# schematic_vibrotactile_driver.net
KiCad netlist of a schematic drawn in EAGLE
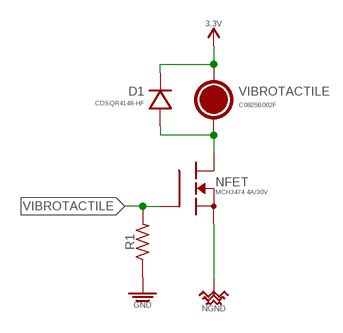
[diagram p0: schematic, sheet 1]

(export (version "E")
  (design (tool "Eeschema 10.0.6"))
  (components
    (comp (ref "D1")
      (value "CDSQR4148-HF")
      (footprint "eagle-import:DFN100X60X55-2")
      (fields (field (name "MFR") "Comchip Technology"))
      (libsource (lib "eagle-import") (part "GENERAL-PURPOSE_SMD-0402_GP_150MA-75V"))
    )
    (comp (ref "NFET")
      (value "MCH3474 4A/30V")
      (footprint "eagle-import:SOTFL65P209X90-3")
      (fields (field (name "MFR") "ON Semiconductor") (field (name "MPN") "MCH3474-TL-W"))
      (libsource (lib "eagle-import") (part "POWER_NCHAN_MCH3474_NMOS_4A-30V"))
    )
    (comp (ref "R1")
      (value "10K")
      (footprint "eagle-import:RESC1005X35_SMD-0402")
      (fields (field (name "MFR") "Yageo") (field (name "MPN") "RC0402JR-0710KP"))
      (libsource (lib "eagle-import") (part "10KΩ_SMD-0402_1/16W-5%"))
    )
    (comp (ref "VIBROTACTILE")
      (value "C0825B002F")
      (footprint "eagle-import:_MOLEX-0530470210_VERT_PITCH-1.25MM")
      (fields (field (name "MFR") "Jinlong Machinery & Electronics, Inc."))
      (libsource (lib "eagle-import") (part "VIBE-MOTOR_CONNECTOR_0530470210_VERT-MALE_PITCH-1.25MM"))
    )
  )
  (nets
    (net (code "1") (name "3.3V") (class "Default")
      (node (ref "D1") (pin "K") (pinfunction "K_K") (pintype "passive"))
      (node (ref "VIBROTACTILE") (pin "1") (pinfunction "+_1") (pintype "passive"))
    )
    (net (code "2") (name "GND") (class "Default")
      (node (ref "R1") (pin "1") (pinfunction "1_1") (pintype "passive"))
    )
    (net (code "3") (name "NGND") (class "Default")
      (node (ref "NFET") (pin "2") (pinfunction "S_2") (pintype "passive"))
    )
    (net (code "4") (name "Net-(NFET-D)") (class "Default")
      (node (ref "D1") (pin "A") (pinfunction "A_A") (pintype "passive"))
      (node (ref "NFET") (pin "3") (pinfunction "D_3") (pintype "passive"))
      (node (ref "VIBROTACTILE") (pin "2") (pinfunction "-_2") (pintype "passive"))
    )
    (net (code "5") (name "VIBROTACTILE") (class "Default")
      (node (ref "NFET") (pin "1") (pinfunction "G_1") (pintype "passive"))
      (node (ref "R1") (pin "2") (pinfunction "2_2") (pintype "passive"))
    )
  )
)
